# e21-hw.net
KiCad netlist of a schematic drawn in EAGLE
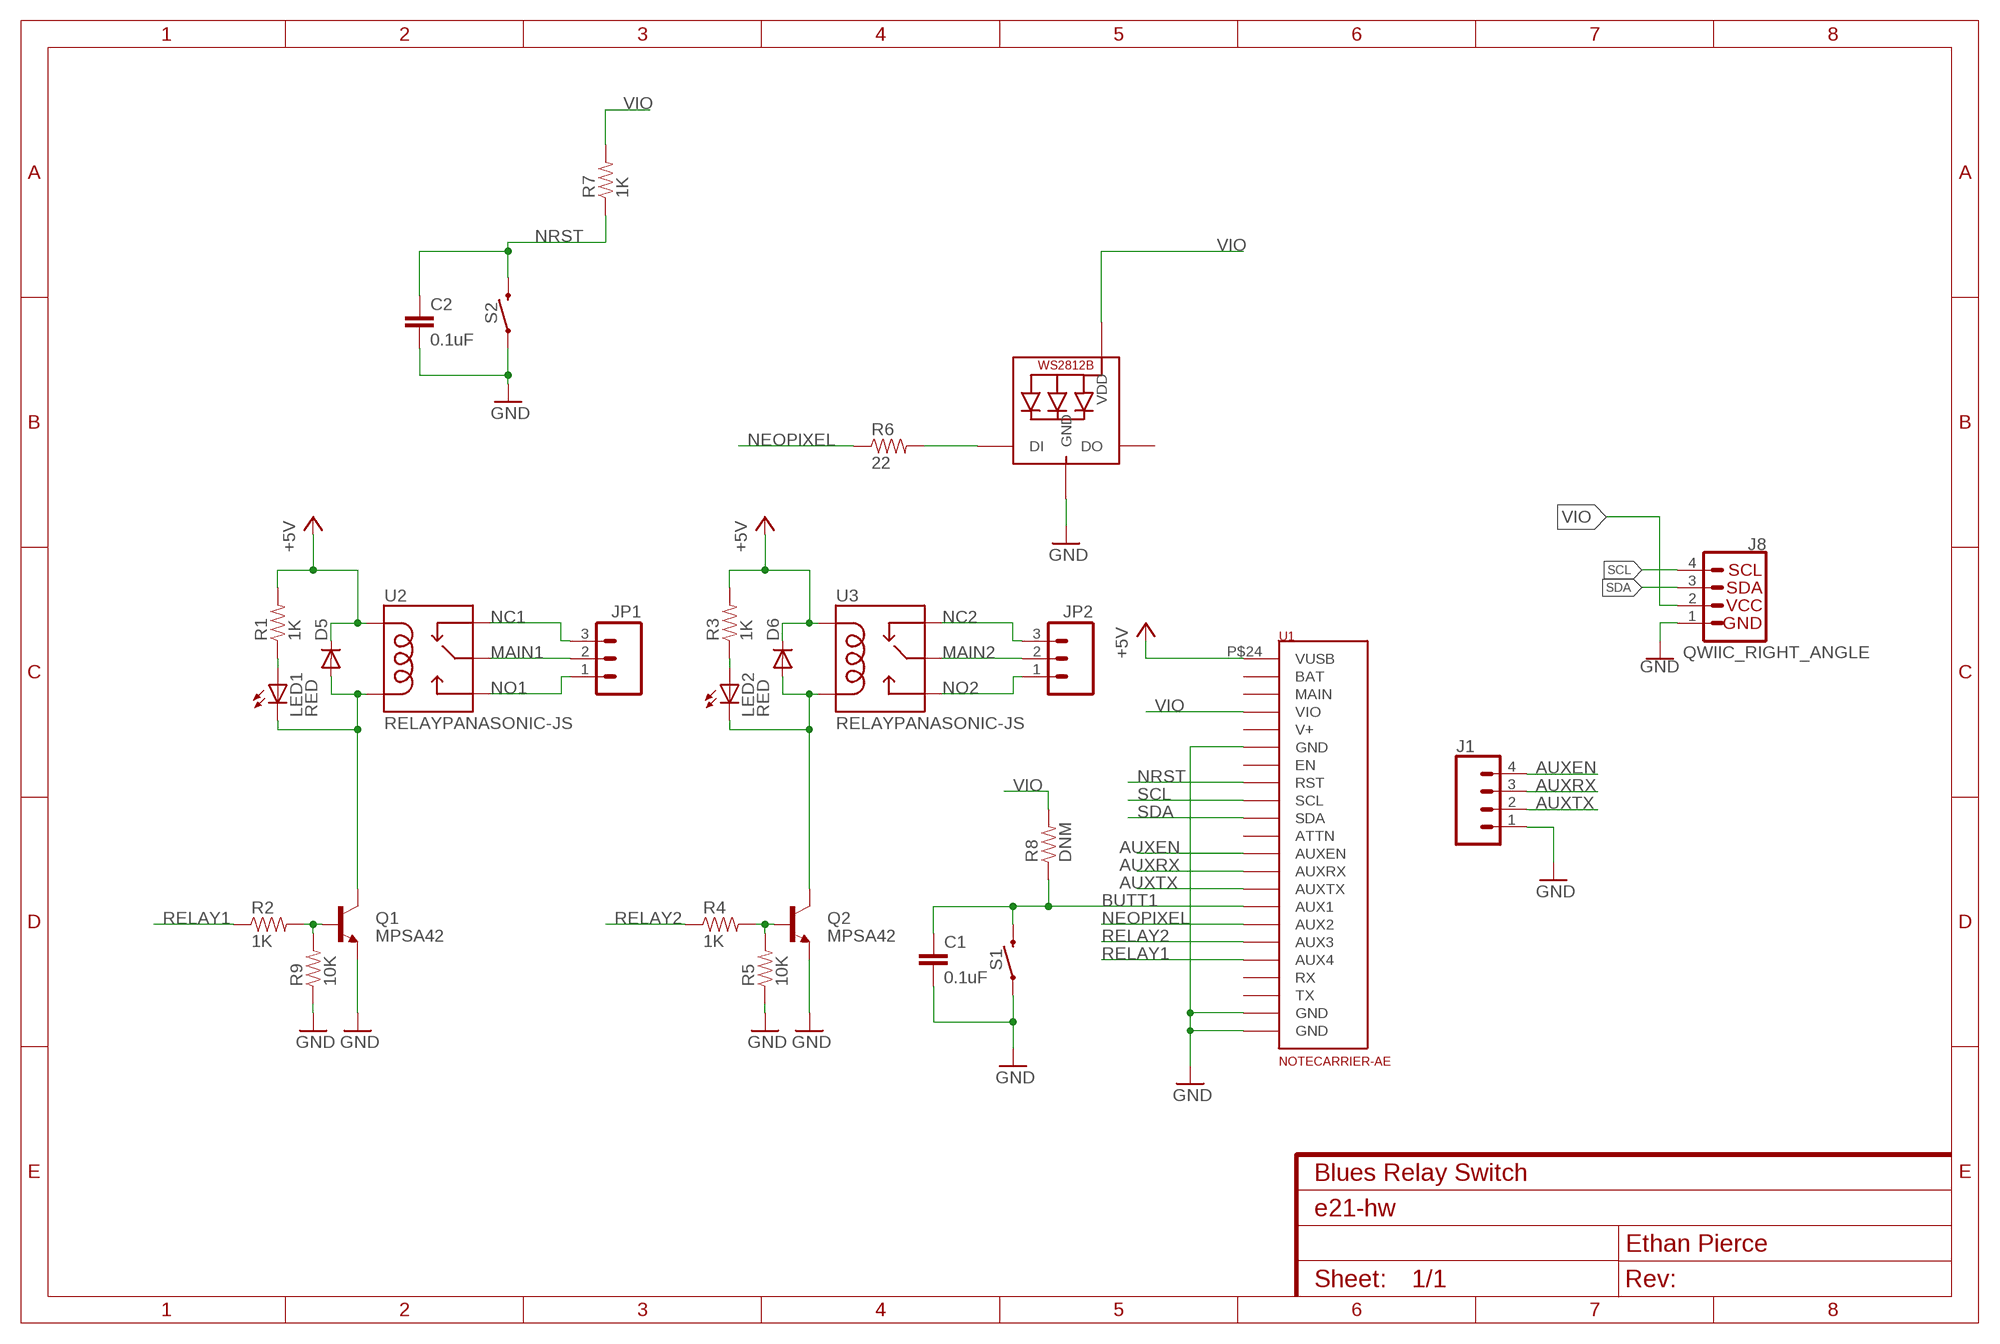
[diagram p0: schematic, sheet 1]

(export (version "E")
  (design (tool "Eeschema 10.0.6"))
  (components
    (comp (ref "C1")
      (value "0.1uF")
      (footprint "eagle-import:0603")
      (libsource (lib "eagle-import") (part "0.1UF-0603-25V-(+80/-20%)"))
    )
    (comp (ref "C2")
      (value "0.1uF")
      (footprint "eagle-import:0603")
      (libsource (lib "eagle-import") (part "0.1UF-0603-25V-(+80/-20%)"))
    )
    (comp (ref "D5")
      (value "DIODE-SOD123")
      (footprint "eagle-import:SOD123")
      (libsource (lib "eagle-import") (part "DIODE-SOD123"))
    )
    (comp (ref "D6")
      (value "DIODE-SOD123")
      (footprint "eagle-import:SOD123")
      (libsource (lib "eagle-import") (part "DIODE-SOD123"))
    )
    (comp (ref "J1")
      (value "CONN_04LOCK")
      (footprint "eagle-import:1X04_LOCK")
      (libsource (lib "eagle-import") (part "CONN_04LOCK"))
    )
    (comp (ref "J8")
      (value "QWIIC_RIGHT_ANGLE")
      (footprint "eagle-import:JST04_1MM_RA")
      (libsource (lib "eagle-import") (part "QWIIC_CONNECTORJS-1MM"))
    )
    (comp (ref "JP1")
      (value "M03-SCREW-5MM")
      (footprint "eagle-import:SCREWTERMINAL-5MM-3")
      (libsource (lib "eagle-import") (part "M03-SCREW-5MM"))
    )
    (comp (ref "JP2")
      (value "M03-SCREW-5MM")
      (footprint "eagle-import:SCREWTERMINAL-5MM-3")
      (libsource (lib "eagle-import") (part "M03-SCREW-5MM"))
    )
    (comp (ref "LED1")
      (value "RED")
      (footprint "eagle-import:LED-0603")
      (libsource (lib "eagle-import") (part "LED0603"))
    )
    (comp (ref "LED2")
      (value "RED")
      (footprint "eagle-import:LED-0603")
      (libsource (lib "eagle-import") (part "LED0603"))
    )
    (comp (ref "LED3")
      (value "WS2812B5050")
      (footprint "eagle-import:WS2812B")
      (libsource (lib "eagle-import") (part "WS2812B5050"))
    )
    (comp (ref "Q1")
      (value "MPSA42")
      (footprint "eagle-import:SOT23")
      (libsource (lib "eagle-import") (part "TRANSISTOR_NPNMPSA42"))
    )
    (comp (ref "Q2")
      (value "MPSA42")
      (footprint "eagle-import:SOT23")
      (libsource (lib "eagle-import") (part "TRANSISTOR_NPNMPSA42"))
    )
    (comp (ref "R1")
      (value "1K")
      (footprint "eagle-import:0603-RES")
      (libsource (lib "eagle-import") (part "RESISTOR0603-RES"))
    )
    (comp (ref "R2")
      (value "1K")
      (footprint "eagle-import:0603-RES")
      (libsource (lib "eagle-import") (part "RESISTOR0603-RES"))
    )
    (comp (ref "R3")
      (value "1K")
      (footprint "eagle-import:0603-RES")
      (libsource (lib "eagle-import") (part "RESISTOR0603-RES"))
    )
    (comp (ref "R4")
      (value "1K")
      (footprint "eagle-import:0603-RES")
      (libsource (lib "eagle-import") (part "RESISTOR0603-RES"))
    )
    (comp (ref "R5")
      (value "10K")
      (footprint "eagle-import:0603-RES")
      (libsource (lib "eagle-import") (part "RESISTOR0603-RES"))
    )
    (comp (ref "R6")
      (value "22")
      (footprint "eagle-import:0603-RES")
      (libsource (lib "eagle-import") (part "RESISTOR0603-RES"))
    )
    (comp (ref "R7")
      (value "1K")
      (footprint "eagle-import:0603-RES")
      (libsource (lib "eagle-import") (part "RESISTOR0603-RES"))
    )
    (comp (ref "R8")
      (value "DNM")
      (footprint "eagle-import:0603-RES")
      (libsource (lib "eagle-import") (part "RESISTOR0603-RES"))
    )
    (comp (ref "R9")
      (value "10K")
      (footprint "eagle-import:0603-RES")
      (libsource (lib "eagle-import") (part "RESISTOR0603-RES"))
    )
    (comp (ref "S1")
      (value "MOMENTARY-SWITCH-SPST-PTH-6.0MM")
      (footprint "eagle-import:TACTILE_SWITCH_PTH_6.0MM")
      (libsource (lib "eagle-import") (part "MOMENTARY-SWITCH-SPST-PTH-6.0MM"))
    )
    (comp (ref "S2")
      (value "MOMENTARY-SWITCH-SPST-PTH-6.0MM")
      (footprint "eagle-import:TACTILE_SWITCH_PTH_6.0MM")
      (libsource (lib "eagle-import") (part "MOMENTARY-SWITCH-SPST-PTH-6.0MM"))
    )
    (comp (ref "U1")
      (value "NOTECARRIER-AE")
      (footprint "eagle-import:NOTECARRIER-AE")
      (libsource (lib "eagle-import") (part "NOTECARRIER-AE"))
    )
    (comp (ref "U2")
      (value "RELAYPANASONIC-JS")
      (footprint "eagle-import:JS1-5V-F")
      (libsource (lib "eagle-import") (part "RELAYPANASONIC-JS"))
    )
    (comp (ref "U3")
      (value "RELAYPANASONIC-JS")
      (footprint "eagle-import:JS1-5V-F")
      (libsource (lib "eagle-import") (part "RELAYPANASONIC-JS"))
    )
  )
  (nets
    (net (code "1") (name "+5V") (class "Default")
      (node (ref "D5") (pin "C") (pinfunction "C_C") (pintype "passive"))
      (node (ref "D6") (pin "C") (pinfunction "C_C") (pintype "passive"))
      (node (ref "R1") (pin "2") (pinfunction "2_2") (pintype "passive"))
      (node (ref "R3") (pin "2") (pinfunction "2_2") (pintype "passive"))
      (node (ref "U1") (pin "P$24") (pinfunction "VUSB_P$24") (pintype "bidirectional"))
      (node (ref "U2") (pin "COIL1") (pinfunction "COIL1_COIL1") (pintype "bidirectional"))
      (node (ref "U3") (pin "COIL1") (pinfunction "COIL1_COIL1") (pintype "bidirectional"))
    )
    (net (code "2") (name "/AUXEN") (class "Default")
      (node (ref "J1") (pin "4") (pinfunction "4_4") (pintype "passive"))
      (node (ref "U1") (pin "P$11") (pinfunction "AUXEN_P$11") (pintype "bidirectional"))
    )
    (net (code "3") (name "/AUXRX") (class "Default")
      (node (ref "J1") (pin "3") (pinfunction "3_3") (pintype "passive"))
      (node (ref "U1") (pin "P$10") (pinfunction "AUXRX_P$10") (pintype "bidirectional"))
    )
    (net (code "4") (name "/AUXTX") (class "Default")
      (node (ref "J1") (pin "2") (pinfunction "2_2") (pintype "passive"))
      (node (ref "U1") (pin "P$9") (pinfunction "AUXTX_P$9") (pintype "bidirectional"))
    )
    (net (code "5") (name "/BUTT1") (class "Default")
      (node (ref "C1") (pin "1") (pinfunction "1_1") (pintype "passive"))
      (node (ref "R8") (pin "1") (pinfunction "1_1") (pintype "passive"))
      (node (ref "S1") (pin "3") (pinfunction "2_3") (pintype "passive"))
      (node (ref "U1") (pin "P$8") (pinfunction "AUX1_P$8") (pintype "bidirectional"))
    )
    (net (code "6") (name "/MAIN1") (class "Default")
      (node (ref "JP1") (pin "2") (pinfunction "2_2") (pintype "passive"))
      (node (ref "U2") (pin "COMMON") (pinfunction "MAIN_COMMON") (pintype "bidirectional"))
    )
    (net (code "7") (name "/MAIN2") (class "Default")
      (node (ref "JP2") (pin "2") (pinfunction "2_2") (pintype "passive"))
      (node (ref "U3") (pin "COMMON") (pinfunction "MAIN_COMMON") (pintype "bidirectional"))
    )
    (net (code "8") (name "/NC1") (class "Default")
      (node (ref "JP1") (pin "3") (pinfunction "3_3") (pintype "passive"))
      (node (ref "U2") (pin "CLOSED") (pinfunction "NC_CLOSED") (pintype "bidirectional"))
    )
    (net (code "9") (name "/NC2") (class "Default")
      (node (ref "JP2") (pin "3") (pinfunction "3_3") (pintype "passive"))
      (node (ref "U3") (pin "CLOSED") (pinfunction "NC_CLOSED") (pintype "bidirectional"))
    )
    (net (code "10") (name "/NEOPIXEL") (class "Default")
      (node (ref "R6") (pin "1") (pinfunction "1_1") (pintype "passive"))
      (node (ref "U1") (pin "P$7") (pinfunction "AUX2_P$7") (pintype "bidirectional"))
    )
    (net (code "11") (name "/NO1") (class "Default")
      (node (ref "JP1") (pin "1") (pinfunction "1_1") (pintype "passive"))
      (node (ref "U2") (pin "OPEN") (pinfunction "NO_OPEN") (pintype "bidirectional"))
    )
    (net (code "12") (name "/NO2") (class "Default")
      (node (ref "JP2") (pin "1") (pinfunction "1_1") (pintype "passive"))
      (node (ref "U3") (pin "OPEN") (pinfunction "NO_OPEN") (pintype "bidirectional"))
    )
    (net (code "13") (name "/NRST") (class "Default")
      (node (ref "C2") (pin "1") (pinfunction "1_1") (pintype "passive"))
      (node (ref "R7") (pin "1") (pinfunction "1_1") (pintype "passive"))
      (node (ref "S2") (pin "3") (pinfunction "2_3") (pintype "passive"))
      (node (ref "U1") (pin "P$16") (pinfunction "RST_P$16") (pintype "bidirectional"))
    )
    (net (code "14") (name "/RELAY1") (class "Default")
      (node (ref "R2") (pin "1") (pinfunction "1_1") (pintype "passive"))
      (node (ref "U1") (pin "P$5") (pinfunction "AUX4_P$5") (pintype "bidirectional"))
    )
    (net (code "15") (name "/RELAY2") (class "Default")
      (node (ref "R4") (pin "1") (pinfunction "1_1") (pintype "passive"))
      (node (ref "U1") (pin "P$6") (pinfunction "AUX3_P$6") (pintype "bidirectional"))
    )
    (net (code "16") (name "GND") (class "Default")
      (node (ref "C1") (pin "2") (pinfunction "2_2") (pintype "passive"))
      (node (ref "C2") (pin "2") (pinfunction "2_2") (pintype "passive"))
      (node (ref "J1") (pin "1") (pinfunction "1_1") (pintype "passive"))
      (node (ref "J8") (pin "1") (pinfunction "1_1") (pintype "power_in"))
      (node (ref "LED3") (pin "3-GND") (pinfunction "GND_3-GND") (pintype "power_in"))
      (node (ref "Q1") (pin "2") (pinfunction "E_2") (pintype "passive"))
      (node (ref "Q2") (pin "2") (pinfunction "E_2") (pintype "passive"))
      (node (ref "R5") (pin "1") (pinfunction "1_1") (pintype "passive"))
      (node (ref "R9") (pin "1") (pinfunction "1_1") (pintype "passive"))
      (node (ref "S1") (pin "1") (pinfunction "1_1") (pintype "passive"))
      (node (ref "S2") (pin "1") (pinfunction "1_1") (pintype "passive"))
      (node (ref "U1") (pin "P$1") (pinfunction "GND_P$1") (pintype "bidirectional"))
      (node (ref "U1") (pin "P$18") (pinfunction "GND_P$18") (pintype "bidirectional"))
      (node (ref "U1") (pin "P$2") (pinfunction "GND_P$2") (pintype "bidirectional"))
    )
    (net (code "17") (name "Net-(LED1-PadA)") (class "Default")
      (node (ref "LED1") (pin "A") (pinfunction "A_A") (pintype "passive"))
      (node (ref "R1") (pin "1") (pinfunction "1_1") (pintype "passive"))
    )
    (net (code "18") (name "Net-(LED2-PadA)") (class "Default")
      (node (ref "LED2") (pin "A") (pinfunction "A_A") (pintype "passive"))
      (node (ref "R3") (pin "1") (pinfunction "1_1") (pintype "passive"))
    )
    (net (code "19") (name "Net-(LED3-DI)") (class "Default")
      (node (ref "LED3") (pin "4-DIN") (pinfunction "DI_4-DIN") (pintype "input"))
      (node (ref "R6") (pin "2") (pinfunction "2_2") (pintype "passive"))
    )
    (net (code "20") (name "Net-(Q1-B)") (class "Default")
      (node (ref "Q1") (pin "1") (pinfunction "B_1") (pintype "passive"))
      (node (ref "R2") (pin "2") (pinfunction "2_2") (pintype "passive"))
      (node (ref "R9") (pin "2") (pinfunction "2_2") (pintype "passive"))
    )
    (net (code "21") (name "Net-(Q1-C)") (class "Default")
      (node (ref "D5") (pin "A") (pinfunction "A_A") (pintype "passive"))
      (node (ref "LED1") (pin "C") (pinfunction "C_C") (pintype "passive"))
      (node (ref "Q1") (pin "3") (pinfunction "C_3") (pintype "passive"))
      (node (ref "U2") (pin "COIL2") (pinfunction "COIL2_COIL2") (pintype "bidirectional"))
    )
    (net (code "22") (name "Net-(Q2-B)") (class "Default")
      (node (ref "Q2") (pin "1") (pinfunction "B_1") (pintype "passive"))
      (node (ref "R4") (pin "2") (pinfunction "2_2") (pintype "passive"))
      (node (ref "R5") (pin "2") (pinfunction "2_2") (pintype "passive"))
    )
    (net (code "23") (name "Net-(Q2-C)") (class "Default")
      (node (ref "D6") (pin "A") (pinfunction "A_A") (pintype "passive"))
      (node (ref "LED2") (pin "C") (pinfunction "C_C") (pintype "passive"))
      (node (ref "Q2") (pin "3") (pinfunction "C_3") (pintype "passive"))
      (node (ref "U3") (pin "COIL2") (pinfunction "COIL2_COIL2") (pintype "bidirectional"))
    )
    (net (code "24") (name "SCL") (class "Default")
      (node (ref "J8") (pin "4") (pinfunction "4_4") (pintype "passive"))
      (node (ref "U1") (pin "P$14") (pinfunction "SCL_P$14") (pintype "bidirectional"))
    )
    (net (code "25") (name "SDA") (class "Default")
      (node (ref "J8") (pin "3") (pinfunction "3_3") (pintype "passive"))
      (node (ref "U1") (pin "P$13") (pinfunction "SDA_P$13") (pintype "bidirectional"))
    )
    (net (code "26") (name "VIO") (class "Default")
      (node (ref "J8") (pin "2") (pinfunction "2_2") (pintype "power_in"))
      (node (ref "LED3") (pin "1-VDD") (pinfunction "VDD_1-VDD") (pintype "power_in"))
      (node (ref "R7") (pin "2") (pinfunction "2_2") (pintype "passive"))
      (node (ref "R8") (pin "2") (pinfunction "2_2") (pintype "passive"))
      (node (ref "U1") (pin "P$21") (pinfunction "VIO_P$21") (pintype "bidirectional"))
    )
    (net (code "27") (name "unconnected-(LED3-DO-Pad2-DOUT)") (class "Default")
      (node (ref "LED3") (pin "2-DOUT") (pinfunction "DO_2-DOUT") (pintype "output"))
    )
    (net (code "28") (name "unconnected-(U1-ATTN-PadP$12)") (class "Default")
      (node (ref "U1") (pin "P$12") (pinfunction "ATTN_P$12") (pintype "bidirectional"))
    )
    (net (code "29") (name "unconnected-(U1-BAT-PadP$23)") (class "Default")
      (node (ref "U1") (pin "P$23") (pinfunction "BAT_P$23") (pintype "bidirectional"))
    )
    (net (code "30") (name "unconnected-(U1-EN-PadP$17)") (class "Default")
      (node (ref "U1") (pin "P$17") (pinfunction "EN_P$17") (pintype "bidirectional"))
    )
    (net (code "31") (name "unconnected-(U1-MAIN-PadP$22)") (class "Default")
      (node (ref "U1") (pin "P$22") (pinfunction "MAIN_P$22") (pintype "bidirectional"))
    )
    (net (code "32") (name "unconnected-(U1-RX-PadP$4)") (class "Default")
      (node (ref "U1") (pin "P$4") (pinfunction "RX_P$4") (pintype "bidirectional"))
    )
    (net (code "33") (name "unconnected-(U1-TX-PadP$3)") (class "Default")
      (node (ref "U1") (pin "P$3") (pinfunction "TX_P$3") (pintype "bidirectional"))
    )
    (net (code "34") (name "unconnected-(U1-V+-PadP$19)") (class "Default")
      (node (ref "U1") (pin "P$19") (pinfunction "V+_P$19") (pintype "bidirectional"))
    )
  )
)
